# ts19390-boost-24mm-driver-mk-1.net
KiCad netlist of a schematic drawn in EAGLE
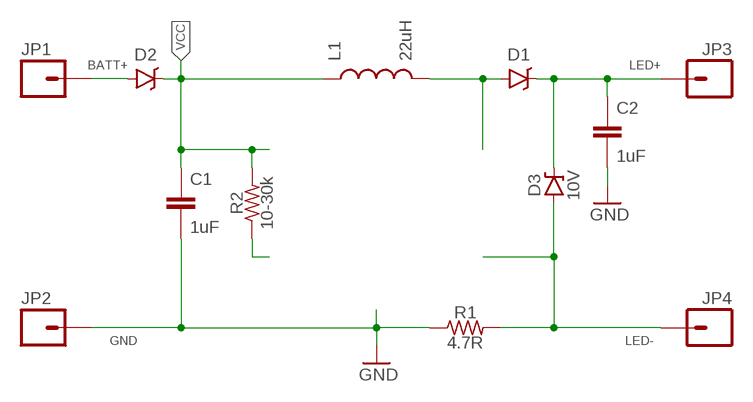
[diagram p0: schematic, sheet 1]

(export (version "E")
  (design (tool "Eeschema 10.0.6"))
  (components
    (comp (ref "C1")
      (value "1uF")
      (footprint "eagle-import:C0805")
      (libsource (lib "eagle-import") (part "CAPACITOR-CERAMICC0805"))
    )
    (comp (ref "C2")
      (value "1uF")
      (footprint "eagle-import:C0805")
      (libsource (lib "eagle-import") (part "CAPACITOR-CERAMICC0805"))
    )
    (comp (ref "D1")
      (value "B340A")
      (footprint "eagle-import:SOD123-SCHOTTKY")
      (libsource (lib "eagle-import") (part "DIODE-SCHOTTKYSOD123"))
    )
    (comp (ref "D2")
      (value "B340A")
      (footprint "eagle-import:SOD123-SCHOTTKY")
      (libsource (lib "eagle-import") (part "DIODE-SCHOTTKYSOD123"))
    )
    (comp (ref "D3")
      (value "10V")
      (footprint "eagle-import:SOD123-ZENER")
      (libsource (lib "eagle-import") (part "DIODE-ZENERSOD123"))
    )
    (comp (ref "JP1")
      (value "M01PTH")
      (footprint "eagle-import:1X01")
      (libsource (lib "eagle-import") (part "M01PTH"))
    )
    (comp (ref "JP2")
      (value "M01PTH")
      (footprint "eagle-import:1X01")
      (libsource (lib "eagle-import") (part "M01PTH"))
    )
    (comp (ref "JP3")
      (value "M01PTH")
      (footprint "eagle-import:1X01")
      (libsource (lib "eagle-import") (part "M01PTH"))
    )
    (comp (ref "JP4")
      (value "M01PTH")
      (footprint "eagle-import:1X01")
      (libsource (lib "eagle-import") (part "M01PTH"))
    )
    (comp (ref "L1")
      (value "22uH")
      (footprint "eagle-import:TAIYO-YUDEN-30XX")
      (libsource (lib "eagle-import") (part "INDUCTORTAIYO-YUDEN-30XX"))
    )
    (comp (ref "R1")
      (value "4.7R")
      (footprint "eagle-import:R0805")
      (libsource (lib "eagle-import") (part "RESISTORR0805"))
    )
    (comp (ref "R2")
      (value "10-30k")
      (footprint "eagle-import:R0603")
      (libsource (lib "eagle-import") (part "RESISTORR0603"))
    )
  )
  (nets
    (net (code "1") (name "/BATT+") (class "Default")
      (node (ref "D2") (pin "A") (pinfunction "A_A") (pintype "passive"))
      (node (ref "JP1") (pin "1") (pinfunction "1_1") (pintype "passive"))
    )
    (net (code "2") (name "/LED+") (class "Default")
      (node (ref "C2") (pin "1") (pinfunction "1_1") (pintype "passive"))
      (node (ref "D1") (pin "C") (pinfunction "C_C") (pintype "passive"))
      (node (ref "D3") (pin "C") (pinfunction "C_C") (pintype "passive"))
      (node (ref "JP3") (pin "1") (pinfunction "1_1") (pintype "passive"))
    )
    (net (code "3") (name "/LED-") (class "Default")
      (node (ref "D3") (pin "A") (pinfunction "A_A") (pintype "passive"))
      (node (ref "JP4") (pin "1") (pinfunction "1_1") (pintype "passive"))
      (node (ref "R1") (pin "2") (pinfunction "2_2") (pintype "passive"))
    )
    (net (code "4") (name "GND") (class "Default")
      (node (ref "C1") (pin "2") (pinfunction "2_2") (pintype "passive"))
      (node (ref "C2") (pin "2") (pinfunction "2_2") (pintype "passive"))
      (node (ref "JP2") (pin "1") (pinfunction "1_1") (pintype "passive"))
      (node (ref "R1") (pin "1") (pinfunction "1_1") (pintype "passive"))
    )
    (net (code "5") (name "Net-(D1-PadA)") (class "Default")
      (node (ref "D1") (pin "A") (pinfunction "A_A") (pintype "passive"))
      (node (ref "L1") (pin "2") (pinfunction "2_2") (pintype "passive"))
    )
    (net (code "6") (name "VCC") (class "Default")
      (node (ref "C1") (pin "1") (pinfunction "1_1") (pintype "passive"))
      (node (ref "D2") (pin "C") (pinfunction "C_C") (pintype "passive"))
      (node (ref "L1") (pin "1") (pinfunction "1_1") (pintype "passive"))
      (node (ref "R2") (pin "2") (pinfunction "2_2") (pintype "passive"))
    )
    (net (code "7") (name "unconnected-(R2-Pad1)") (class "Default")
      (node (ref "R2") (pin "1") (pinfunction "1_1") (pintype "passive"))
    )
  )
)
